# ATtiny43U_Study_50x31.net
KiCad netlist of a schematic drawn in EAGLE
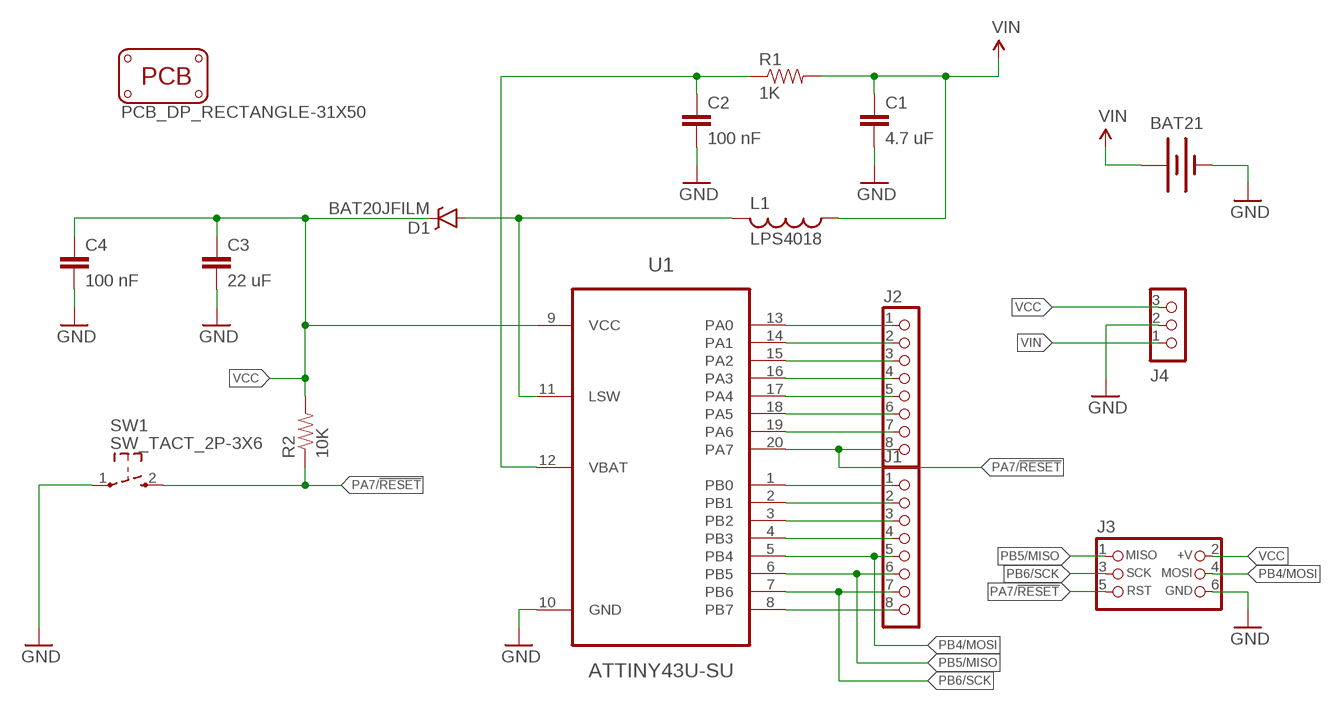
[diagram p0: schematic, sheet 1]

(export (version "E")
  (design (tool "Eeschema 10.0.6"))
  (components
    (comp (ref "BAT21")
      (value "BATTERYAAA")
      (footprint "eagle-import:BATTERY-AAA")
      (libsource (lib "eagle-import") (part "BATTERYAAA"))
    )
    (comp (ref "C1")
      (value "4.7 uF")
      (footprint "eagle-import:0805")
      (fields (field (name "PARTNO") "GRM219R60J475KE19"))
      (libsource (lib "eagle-import") (part "CAP0805"))
    )
    (comp (ref "C2")
      (value "100 nF")
      (footprint "eagle-import:0603-CAP")
      (libsource (lib "eagle-import") (part "CAP0603-CAP"))
    )
    (comp (ref "C3")
      (value "22 uF")
      (footprint "eagle-import:0805")
      (fields (field (name "PARTNO") "GRM21BR60J226ME39"))
      (libsource (lib "eagle-import") (part "CAP0805"))
    )
    (comp (ref "C4")
      (value "100 nF")
      (footprint "eagle-import:0603-CAP")
      (libsource (lib "eagle-import") (part "CAP0603-CAP"))
    )
    (comp (ref "D1")
      (value "BAT20JFILM")
      (footprint "eagle-import:SOD-323")
      (fields (field (name "PARTNO") "PMEG2005EJ"))
      (libsource (lib "eagle-import") (part "BAT20JFILM"))
    )
    (comp (ref "J1")
      (value "CON_HEADER_1X08-PTH")
      (footprint "eagle-import:M1X8")
      (libsource (lib "eagle-import") (part "CON_HEADER_1X08-PTH"))
    )
    (comp (ref "J2")
      (value "CON_HEADER_1X08-PTH")
      (footprint "eagle-import:M1X8")
      (libsource (lib "eagle-import") (part "CON_HEADER_1X08-PTH"))
    )
    (comp (ref "J3")
      (value "CON_HEADER_PRG_AVR_ICSP-PTH")
      (footprint "eagle-import:HEADER_PRG_2X03")
      (libsource (lib "eagle-import") (part "CON_HEADER_PRG_AVR_ICSP-PTH"))
    )
    (comp (ref "J4")
      (value "CON_HEADER_1X03-PTH")
      (footprint "eagle-import:M1X3")
      (libsource (lib "eagle-import") (part "CON_HEADER_1X03-PTH"))
    )
    (comp (ref "L1")
      (value "LPS4018")
      (footprint "eagle-import:LPS4018")
      (fields (field (name "PARTNO") "LPS4018-153MRB"))
      (libsource (lib "eagle-import") (part "LPS4018"))
    )
    (comp (ref "PCB2")
      (value "PCB_DP_RECTANGLE-31X50")
      (footprint "eagle-import:DP5031_V1")
      (libsource (lib "eagle-import") (part "PCB_DP_RECTANGLE-31X50"))
    )
    (comp (ref "R1")
      (value "1K")
      (footprint "eagle-import:0603-RES")
      (libsource (lib "eagle-import") (part "1KOHM-1/10W-1%(0603)"))
    )
    (comp (ref "R2")
      (value "10K")
      (footprint "eagle-import:0603-RES")
      (libsource (lib "eagle-import") (part "1KOHM-1/10W-1%(0603)"))
    )
    (comp (ref "SW1")
      (value "SW_TACT_2P-3X6")
      (footprint "eagle-import:SW_TACT_3X6")
      (libsource (lib "eagle-import") (part "SW_TACT_2P-3X6"))
    )
    (comp (ref "U1")
      (value "ATTINY43U-SU")
      (footprint "eagle-import:20S2")
      (libsource (lib "eagle-import") (part "ATTINY43USU-"))
    )
  )
  (nets
    (net (code "1") (name "/PA7{slash}~{RESET}") (class "Default")
      (node (ref "J2") (pin "8") (pinfunction "8_8") (pintype "passive"))
      (node (ref "J3") (pin "5") (pinfunction "RST_5") (pintype "passive"))
      (node (ref "R2") (pin "1") (pinfunction "1_1") (pintype "passive"))
      (node (ref "SW1") (pin "2") (pinfunction "3_2") (pintype "passive"))
      (node (ref "U1") (pin "20") (pinfunction "PA7_20") (pintype "bidirectional"))
    )
    (net (code "2") (name "GND") (class "Default")
      (node (ref "BAT21") (pin "GND@1") (pinfunction "-_GND@1") (pintype "power_in"))
      (node (ref "C1") (pin "2") (pinfunction "2_2") (pintype "passive"))
      (node (ref "C2") (pin "2") (pinfunction "2_2") (pintype "passive"))
      (node (ref "C3") (pin "2") (pinfunction "2_2") (pintype "passive"))
      (node (ref "C4") (pin "2") (pinfunction "2_2") (pintype "passive"))
      (node (ref "J3") (pin "6") (pinfunction "GND_6") (pintype "passive"))
      (node (ref "J4") (pin "2") (pinfunction "2_2") (pintype "bidirectional"))
      (node (ref "SW1") (pin "1") (pinfunction "1_1") (pintype "passive"))
      (node (ref "U1") (pin "10") (pinfunction "GND_10") (pintype "passive"))
    )
    (net (code "3") (name "Net-(L1-2)") (class "Default")
      (node (ref "D1") (pin "A") (pinfunction "A_A") (pintype "passive"))
      (node (ref "L1") (pin "P$2") (pinfunction "2_P$2") (pintype "passive"))
      (node (ref "U1") (pin "11") (pinfunction "LSW_11") (pintype "passive"))
    )
    (net (code "4") (name "Net-(U1-PA0)") (class "Default")
      (node (ref "J2") (pin "1") (pinfunction "1_1") (pintype "passive"))
      (node (ref "U1") (pin "13") (pinfunction "PA0_13") (pintype "bidirectional"))
    )
    (net (code "5") (name "Net-(U1-PA1)") (class "Default")
      (node (ref "J2") (pin "2") (pinfunction "2_2") (pintype "passive"))
      (node (ref "U1") (pin "14") (pinfunction "PA1_14") (pintype "bidirectional"))
    )
    (net (code "6") (name "Net-(U1-PA2)") (class "Default")
      (node (ref "J2") (pin "3") (pinfunction "3_3") (pintype "passive"))
      (node (ref "U1") (pin "15") (pinfunction "PA2_15") (pintype "bidirectional"))
    )
    (net (code "7") (name "Net-(U1-PA3)") (class "Default")
      (node (ref "J2") (pin "4") (pinfunction "4_4") (pintype "passive"))
      (node (ref "U1") (pin "16") (pinfunction "PA3_16") (pintype "bidirectional"))
    )
    (net (code "8") (name "Net-(U1-PA4)") (class "Default")
      (node (ref "J2") (pin "5") (pinfunction "5_5") (pintype "passive"))
      (node (ref "U1") (pin "17") (pinfunction "PA4_17") (pintype "bidirectional"))
    )
    (net (code "9") (name "Net-(U1-PA5)") (class "Default")
      (node (ref "J2") (pin "6") (pinfunction "6_6") (pintype "passive"))
      (node (ref "U1") (pin "18") (pinfunction "PA5_18") (pintype "bidirectional"))
    )
    (net (code "10") (name "Net-(U1-PA6)") (class "Default")
      (node (ref "J2") (pin "7") (pinfunction "7_7") (pintype "passive"))
      (node (ref "U1") (pin "19") (pinfunction "PA6_19") (pintype "bidirectional"))
    )
    (net (code "11") (name "Net-(U1-PB0)") (class "Default")
      (node (ref "J1") (pin "1") (pinfunction "1_1") (pintype "passive"))
      (node (ref "U1") (pin "1") (pinfunction "PB0_1") (pintype "bidirectional"))
    )
    (net (code "12") (name "Net-(U1-PB1)") (class "Default")
      (node (ref "J1") (pin "2") (pinfunction "2_2") (pintype "passive"))
      (node (ref "U1") (pin "2") (pinfunction "PB1_2") (pintype "bidirectional"))
    )
    (net (code "13") (name "Net-(U1-PB2)") (class "Default")
      (node (ref "J1") (pin "3") (pinfunction "3_3") (pintype "passive"))
      (node (ref "U1") (pin "3") (pinfunction "PB2_3") (pintype "bidirectional"))
    )
    (net (code "14") (name "Net-(U1-PB3)") (class "Default")
      (node (ref "J1") (pin "4") (pinfunction "4_4") (pintype "passive"))
      (node (ref "U1") (pin "4") (pinfunction "PB3_4") (pintype "bidirectional"))
    )
    (net (code "15") (name "Net-(U1-PB7)") (class "Default")
      (node (ref "J1") (pin "8") (pinfunction "8_8") (pintype "passive"))
      (node (ref "U1") (pin "8") (pinfunction "PB7_8") (pintype "bidirectional"))
    )
    (net (code "16") (name "Net-(U1-VBAT)") (class "Default")
      (node (ref "C2") (pin "1") (pinfunction "1_1") (pintype "passive"))
      (node (ref "R1") (pin "1") (pinfunction "1_1") (pintype "passive"))
      (node (ref "U1") (pin "12") (pinfunction "VBAT_12") (pintype "passive"))
    )
    (net (code "17") (name "PB4{slash}MOSI") (class "Default")
      (node (ref "J1") (pin "5") (pinfunction "5_5") (pintype "passive"))
      (node (ref "J3") (pin "4") (pinfunction "MOSI_4") (pintype "passive"))
      (node (ref "U1") (pin "5") (pinfunction "PB4_5") (pintype "bidirectional"))
    )
    (net (code "18") (name "PB5{slash}MISO") (class "Default")
      (node (ref "J1") (pin "6") (pinfunction "6_6") (pintype "passive"))
      (node (ref "J3") (pin "1") (pinfunction "MISO_1") (pintype "passive"))
      (node (ref "U1") (pin "6") (pinfunction "PB5_6") (pintype "bidirectional"))
    )
    (net (code "19") (name "PB6{slash}SCK") (class "Default")
      (node (ref "J1") (pin "7") (pinfunction "7_7") (pintype "passive"))
      (node (ref "J3") (pin "3") (pinfunction "SCK_3") (pintype "passive"))
      (node (ref "U1") (pin "7") (pinfunction "PB6_7") (pintype "bidirectional"))
    )
    (net (code "20") (name "VCC") (class "Default")
      (node (ref "C3") (pin "1") (pinfunction "1_1") (pintype "passive"))
      (node (ref "C4") (pin "1") (pinfunction "1_1") (pintype "passive"))
      (node (ref "D1") (pin "C") (pinfunction "C_C") (pintype "passive"))
      (node (ref "J3") (pin "2") (pinfunction "+V_2") (pintype "passive"))
      (node (ref "J4") (pin "3") (pinfunction "3_3") (pintype "bidirectional"))
      (node (ref "R2") (pin "2") (pinfunction "2_2") (pintype "passive"))
      (node (ref "U1") (pin "9") (pinfunction "VCC_9") (pintype "power_in"))
    )
    (net (code "21") (name "VIN") (class "Default")
      (node (ref "BAT21") (pin "PWR@1") (pinfunction "+_PWR@1") (pintype "power_in"))
      (node (ref "C1") (pin "1") (pinfunction "1_1") (pintype "passive"))
      (node (ref "J4") (pin "1") (pinfunction "1_1") (pintype "bidirectional"))
      (node (ref "L1") (pin "P$1") (pinfunction "1_P$1") (pintype "passive"))
      (node (ref "R1") (pin "2") (pinfunction "2_2") (pintype "passive"))
    )
  )
)
